# adc.net
KiCad netlist of a schematic drawn in EAGLE
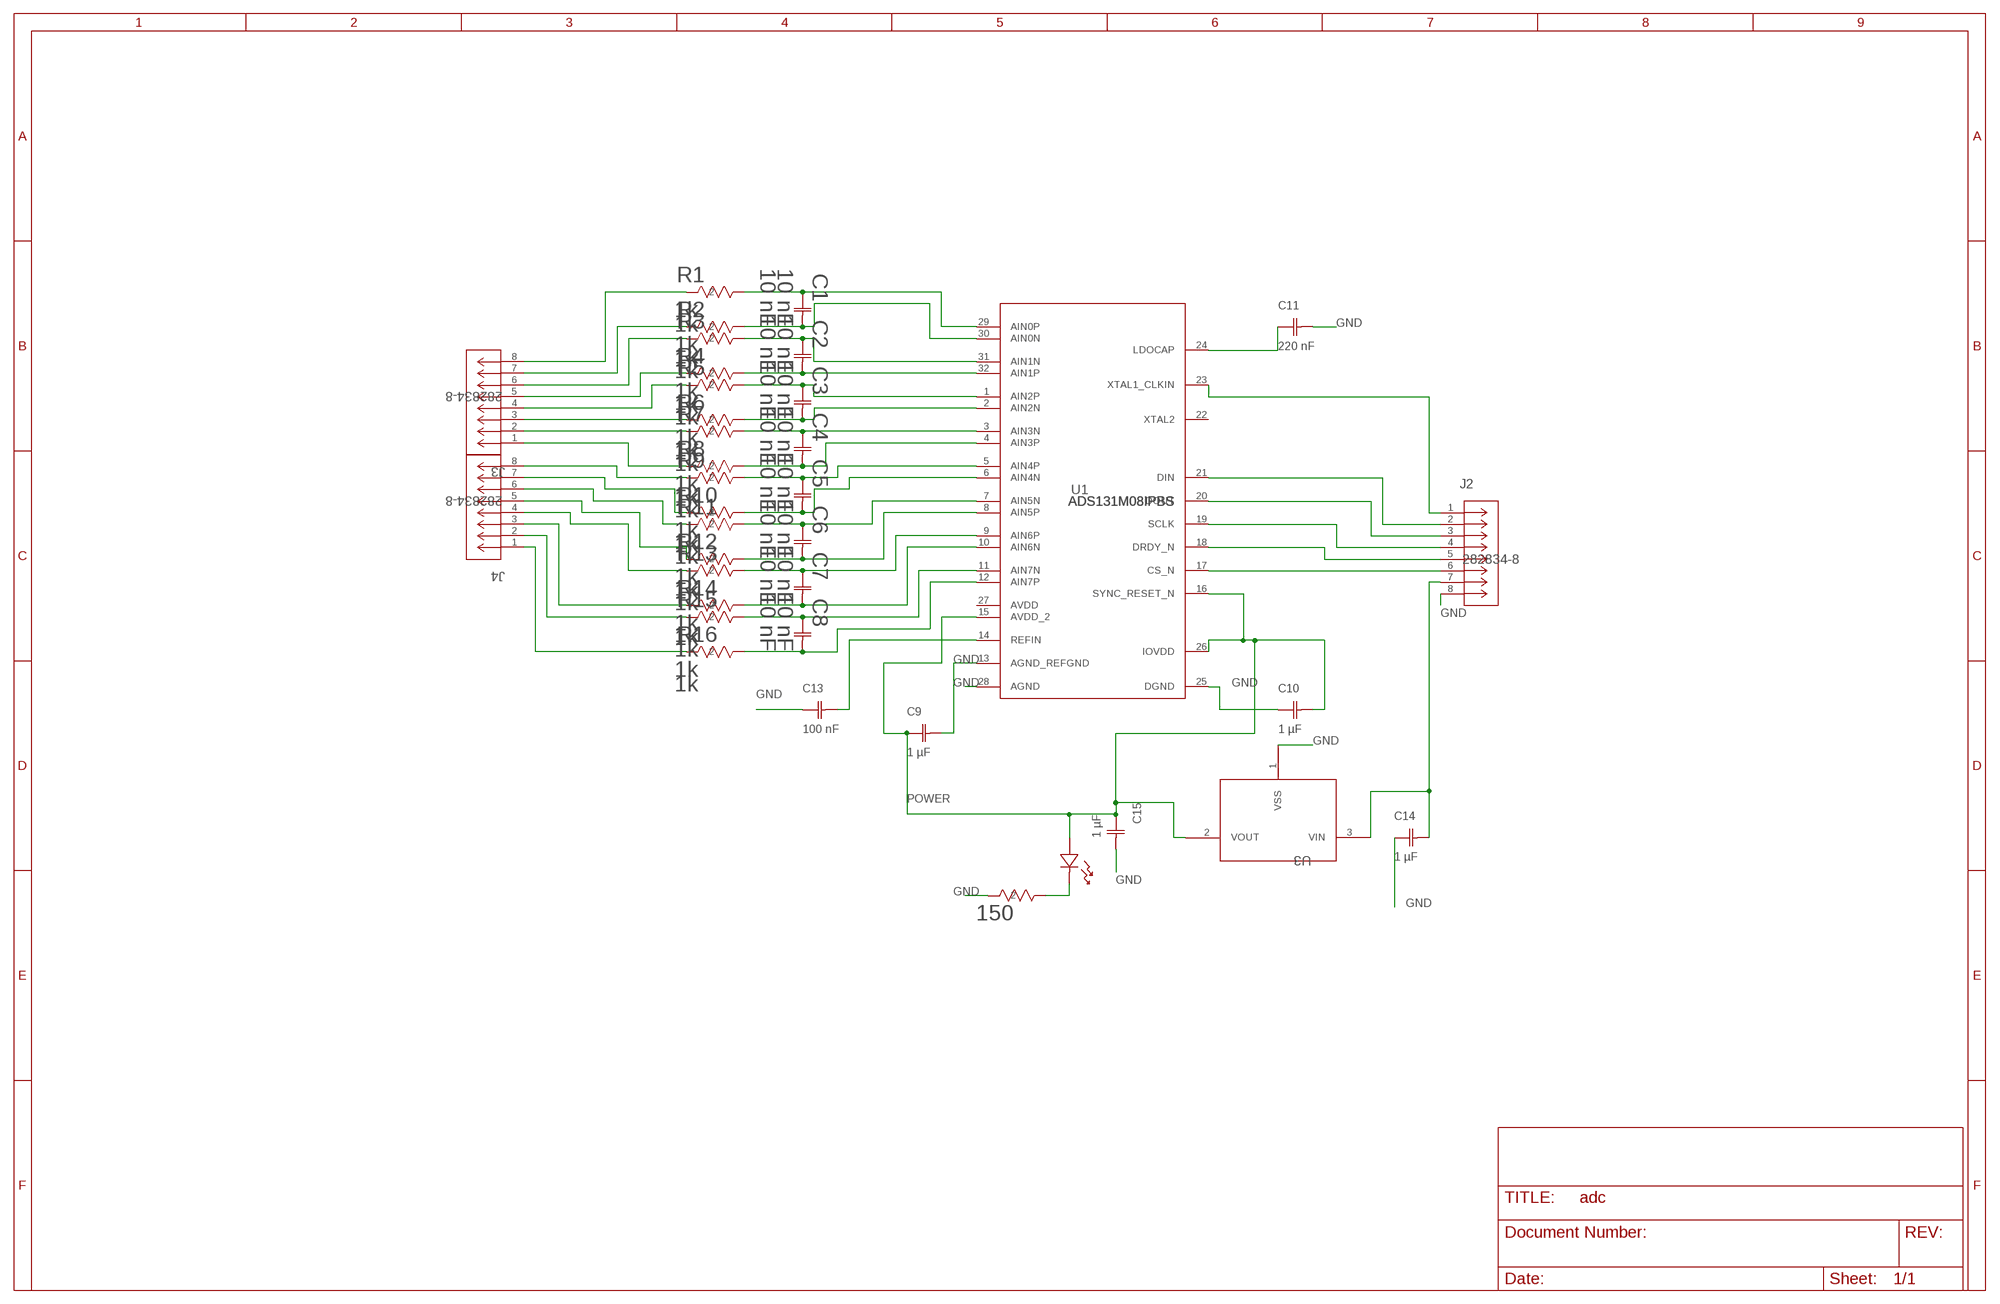
[diagram p0: schematic, sheet 1]

(export (version "E")
  (design (tool "Eeschema 10.0.6"))
  (components
    (comp (ref "C1")
      (value "10 nF")
      (footprint "eagle-import:CAPC220145_88N_KEM")
      (fields
        (field (name "MANUFACTURER_PART_NUMBER") "C0805C103K5RACAUTO")
        (field (name "COPYRIGHT") "Copyright (C) 2025 Ultra Librarian. All rights reserved.")
      )
      (libsource (lib "eagle-import") (part "C0805C103K5RACAUTO"))
    )
    (comp (ref "C2")
      (value "10 nF")
      (footprint "eagle-import:CAPC220145_88N_KEM")
      (fields
        (field (name "MANUFACTURER_PART_NUMBER") "C0805C103K5RACAUTO")
        (field (name "COPYRIGHT") "Copyright (C) 2025 Ultra Librarian. All rights reserved.")
      )
      (libsource (lib "eagle-import") (part "C0805C103K5RACAUTO"))
    )
    (comp (ref "C3")
      (value "10 nF")
      (footprint "eagle-import:CAPC220145_88N_KEM")
      (fields
        (field (name "MANUFACTURER_PART_NUMBER") "C0805C103K5RACAUTO")
        (field (name "COPYRIGHT") "Copyright (C) 2025 Ultra Librarian. All rights reserved.")
      )
      (libsource (lib "eagle-import") (part "C0805C103K5RACAUTO"))
    )
    (comp (ref "C4")
      (value "10 nF")
      (footprint "eagle-import:CAPC220145_88N_KEM")
      (fields
        (field (name "MANUFACTURER_PART_NUMBER") "C0805C103K5RACAUTO")
        (field (name "COPYRIGHT") "Copyright (C) 2025 Ultra Librarian. All rights reserved.")
      )
      (libsource (lib "eagle-import") (part "C0805C103K5RACAUTO"))
    )
    (comp (ref "C5")
      (value "10 nF")
      (footprint "eagle-import:CAPC220145_88N_KEM")
      (fields
        (field (name "MANUFACTURER_PART_NUMBER") "C0805C103K5RACAUTO")
        (field (name "COPYRIGHT") "Copyright (C) 2025 Ultra Librarian. All rights reserved.")
      )
      (libsource (lib "eagle-import") (part "C0805C103K5RACAUTO"))
    )
    (comp (ref "C6")
      (value "10 nF")
      (footprint "eagle-import:CAPC220145_88N_KEM")
      (fields
        (field (name "MANUFACTURER_PART_NUMBER") "C0805C103K5RACAUTO")
        (field (name "COPYRIGHT") "Copyright (C) 2025 Ultra Librarian. All rights reserved.")
      )
      (libsource (lib "eagle-import") (part "C0805C103K5RACAUTO"))
    )
    (comp (ref "C7")
      (value "10 nF")
      (footprint "eagle-import:CAPC220145_88N_KEM")
      (fields
        (field (name "MANUFACTURER_PART_NUMBER") "C0805C103K5RACAUTO")
        (field (name "COPYRIGHT") "Copyright (C) 2025 Ultra Librarian. All rights reserved.")
      )
      (libsource (lib "eagle-import") (part "C0805C103K5RACAUTO"))
    )
    (comp (ref "C8")
      (value "10 nF")
      (footprint "eagle-import:CAPC220145_88N_KEM")
      (fields
        (field (name "MANUFACTURER_PART_NUMBER") "C0805C103K5RACAUTO")
        (field (name "COPYRIGHT") "Copyright (C) 2025 Ultra Librarian. All rights reserved.")
      )
      (libsource (lib "eagle-import") (part "C0805C103K5RACAUTO"))
    )
    (comp (ref "C9")
      (value "1 µF")
      (footprint "eagle-import:CAPC220145_140N_KEM")
      (fields
        (field (name "MANUFACTURER_PART_NUMBER") "C0805C105K5RACTU")
        (field (name "COPYRIGHT") "Copyright (C) 2025 Ultra Librarian. All rights reserved.")
      )
      (libsource (lib "eagle-import") (part "C0805C105K5RACTU"))
    )
    (comp (ref "C10")
      (value "1 µF")
      (footprint "eagle-import:CAPC220145_140N_KEM")
      (fields
        (field (name "MANUFACTURER_PART_NUMBER") "C0805C105K5RACTU")
        (field (name "COPYRIGHT") "Copyright (C) 2025 Ultra Librarian. All rights reserved.")
      )
      (libsource (lib "eagle-import") (part "C0805C105K5RACTU"))
    )
    (comp (ref "C11")
      (value "220 nF")
      (footprint "eagle-import:CAPC220145_100N_KEM")
      (fields
        (field (name "MANUFACTURER_PART_NUMBER") "C0805C224K5RACAUTO")
        (field (name "COPYRIGHT") "Copyright (C) 2025 Ultra Librarian. All rights reserved.")
      )
      (libsource (lib "eagle-import") (part "C0805C224K5RACAUTO"))
    )
    (comp (ref "C13")
      (value "100 nF")
      (footprint "eagle-import:CAPC220145_88N_KEM")
      (fields
        (field (name "MANUFACTURER_PART_NUMBER") "C0805C104K5RACTU")
        (field (name "COPYRIGHT") "Copyright (C) 2025 Ultra Librarian. All rights reserved.")
      )
      (libsource (lib "eagle-import") (part "C0805C104K5RACTU"))
    )
    (comp (ref "C14")
      (value "1 µF")
      (footprint "eagle-import:CAPC220145_140N_KEM")
      (fields
        (field (name "MANUFACTURER_PART_NUMBER") "C0805C105K5RACTU")
        (field (name "COPYRIGHT") "Copyright (C) 2025 Ultra Librarian. All rights reserved.")
      )
      (libsource (lib "eagle-import") (part "C0805C105K5RACTU"))
    )
    (comp (ref "C15")
      (value "1 µF")
      (footprint "eagle-import:CAPC220145_140N_KEM")
      (fields
        (field (name "MANUFACTURER_PART_NUMBER") "C0805C105K5RACTU")
        (field (name "COPYRIGHT") "Copyright (C) 2025 Ultra Librarian. All rights reserved.")
      )
      (libsource (lib "eagle-import") (part "C0805C105K5RACTU"))
    )
    (comp (ref "J2")
      (value "282834-8")
      (footprint "eagle-import:CONN_282834-8_TEC")
      (fields (field (name "COPYRIGHT") "Copyright (C) 2025 Ultra Librarian. All rights reserved."))
      (libsource (lib "eagle-import") (part "282834-8"))
    )
    (comp (ref "J3")
      (value "282834-8")
      (footprint "eagle-import:CONN_282834-8_TEC")
      (fields (field (name "COPYRIGHT") "Copyright (C) 2025 Ultra Librarian. All rights reserved."))
      (libsource (lib "eagle-import") (part "282834-8"))
    )
    (comp (ref "J4")
      (value "282834-8")
      (footprint "eagle-import:CONN_282834-8_TEC")
      (fields (field (name "COPYRIGHT") "Copyright (C) 2025 Ultra Librarian. All rights reserved."))
      (libsource (lib "eagle-import") (part "282834-8"))
    )
    (comp (ref "LED1")
      (value "LTST-C190KFKT")
      (footprint "eagle-import:LED_LSTS-C190_LTO")
      (fields (field (name "COPYRIGHT") "Copyright (C) 2025 Ultra Librarian. All rights reserved."))
      (libsource (lib "eagle-import") (part "LTST-C190KFKT"))
    )
    (comp (ref "R1")
      (value "1k")
      (footprint "eagle-import:RC0402N_YAG-M")
      (fields
        (field (name "MANUFACTURER_PART_NUMBER") "RC0402JR-071KL")
        (field (name "COPYRIGHT") "Copyright (C) 2025 Ultra Librarian. All rights reserved.")
      )
      (libsource (lib "eagle-import") (part "RC0402JR-071KLRC0402N_YAG-M"))
    )
    (comp (ref "R2")
      (value "1k")
      (footprint "eagle-import:RC0402N_YAG-M")
      (fields
        (field (name "MANUFACTURER_PART_NUMBER") "RC0402JR-071KL")
        (field (name "COPYRIGHT") "Copyright (C) 2025 Ultra Librarian. All rights reserved.")
      )
      (libsource (lib "eagle-import") (part "RC0402JR-071KLRC0402N_YAG-M"))
    )
    (comp (ref "R3")
      (value "1k")
      (footprint "eagle-import:RC0402N_YAG-M")
      (fields
        (field (name "MANUFACTURER_PART_NUMBER") "RC0402JR-071KL")
        (field (name "COPYRIGHT") "Copyright (C) 2025 Ultra Librarian. All rights reserved.")
      )
      (libsource (lib "eagle-import") (part "RC0402JR-071KLRC0402N_YAG-M"))
    )
    (comp (ref "R4")
      (value "1k")
      (footprint "eagle-import:RC0402N_YAG-M")
      (fields
        (field (name "MANUFACTURER_PART_NUMBER") "RC0402JR-071KL")
        (field (name "COPYRIGHT") "Copyright (C) 2025 Ultra Librarian. All rights reserved.")
      )
      (libsource (lib "eagle-import") (part "RC0402JR-071KLRC0402N_YAG-M"))
    )
    (comp (ref "R5")
      (value "1k")
      (footprint "eagle-import:RC0402N_YAG-M")
      (fields
        (field (name "MANUFACTURER_PART_NUMBER") "RC0402JR-071KL")
        (field (name "COPYRIGHT") "Copyright (C) 2025 Ultra Librarian. All rights reserved.")
      )
      (libsource (lib "eagle-import") (part "RC0402JR-071KLRC0402N_YAG-M"))
    )
    (comp (ref "R6")
      (value "1k")
      (footprint "eagle-import:RC0402N_YAG-M")
      (fields
        (field (name "MANUFACTURER_PART_NUMBER") "RC0402JR-071KL")
        (field (name "COPYRIGHT") "Copyright (C) 2025 Ultra Librarian. All rights reserved.")
      )
      (libsource (lib "eagle-import") (part "RC0402JR-071KLRC0402N_YAG-M"))
    )
    (comp (ref "R7")
      (value "1k")
      (footprint "eagle-import:RC0402N_YAG-M")
      (fields
        (field (name "MANUFACTURER_PART_NUMBER") "RC0402JR-071KL")
        (field (name "COPYRIGHT") "Copyright (C) 2025 Ultra Librarian. All rights reserved.")
      )
      (libsource (lib "eagle-import") (part "RC0402JR-071KLRC0402N_YAG-M"))
    )
    (comp (ref "R8")
      (value "1k")
      (footprint "eagle-import:RC0402N_YAG-M")
      (fields
        (field (name "MANUFACTURER_PART_NUMBER") "RC0402JR-071KL")
        (field (name "COPYRIGHT") "Copyright (C) 2025 Ultra Librarian. All rights reserved.")
      )
      (libsource (lib "eagle-import") (part "RC0402JR-071KLRC0402N_YAG-M"))
    )
    (comp (ref "R9")
      (value "1k")
      (footprint "eagle-import:RC0402N_YAG-M")
      (fields
        (field (name "MANUFACTURER_PART_NUMBER") "RC0402JR-071KL")
        (field (name "COPYRIGHT") "Copyright (C) 2025 Ultra Librarian. All rights reserved.")
      )
      (libsource (lib "eagle-import") (part "RC0402JR-071KLRC0402N_YAG-M"))
    )
    (comp (ref "R10")
      (value "1k")
      (footprint "eagle-import:RC0402N_YAG-M")
      (fields
        (field (name "MANUFACTURER_PART_NUMBER") "RC0402JR-071KL")
        (field (name "COPYRIGHT") "Copyright (C) 2025 Ultra Librarian. All rights reserved.")
      )
      (libsource (lib "eagle-import") (part "RC0402JR-071KLRC0402N_YAG-M"))
    )
    (comp (ref "R11")
      (value "1k")
      (footprint "eagle-import:RC0402N_YAG-M")
      (fields
        (field (name "MANUFACTURER_PART_NUMBER") "RC0402JR-071KL")
        (field (name "COPYRIGHT") "Copyright (C) 2025 Ultra Librarian. All rights reserved.")
      )
      (libsource (lib "eagle-import") (part "RC0402JR-071KLRC0402N_YAG-M"))
    )
    (comp (ref "R12")
      (value "1k")
      (footprint "eagle-import:RC0402N_YAG-M")
      (fields
        (field (name "MANUFACTURER_PART_NUMBER") "RC0402JR-071KL")
        (field (name "COPYRIGHT") "Copyright (C) 2025 Ultra Librarian. All rights reserved.")
      )
      (libsource (lib "eagle-import") (part "RC0402JR-071KLRC0402N_YAG-M"))
    )
    (comp (ref "R13")
      (value "1k")
      (footprint "eagle-import:RC0402N_YAG-M")
      (fields
        (field (name "MANUFACTURER_PART_NUMBER") "RC0402JR-071KL")
        (field (name "COPYRIGHT") "Copyright (C) 2025 Ultra Librarian. All rights reserved.")
      )
      (libsource (lib "eagle-import") (part "RC0402JR-071KLRC0402N_YAG-M"))
    )
    (comp (ref "R14")
      (value "1k")
      (footprint "eagle-import:RC0402N_YAG-M")
      (fields
        (field (name "MANUFACTURER_PART_NUMBER") "RC0402JR-071KL")
        (field (name "COPYRIGHT") "Copyright (C) 2025 Ultra Librarian. All rights reserved.")
      )
      (libsource (lib "eagle-import") (part "RC0402JR-071KLRC0402N_YAG-M"))
    )
    (comp (ref "R15")
      (value "1k")
      (footprint "eagle-import:RC0402N_YAG-M")
      (fields
        (field (name "MANUFACTURER_PART_NUMBER") "RC0402JR-071KL")
        (field (name "COPYRIGHT") "Copyright (C) 2025 Ultra Librarian. All rights reserved.")
      )
      (libsource (lib "eagle-import") (part "RC0402JR-071KLRC0402N_YAG-M"))
    )
    (comp (ref "R16")
      (value "1k")
      (footprint "eagle-import:RC0402N_YAG-M")
      (fields
        (field (name "MANUFACTURER_PART_NUMBER") "RC0402JR-071KL")
        (field (name "COPYRIGHT") "Copyright (C) 2025 Ultra Librarian. All rights reserved.")
      )
      (libsource (lib "eagle-import") (part "RC0402JR-071KLRC0402N_YAG-M"))
    )
    (comp (ref "R18")
      (value "150")
      (footprint "eagle-import:RC0402N_YAG-M")
      (fields
        (field (name "MANUFACTURER_PART_NUMBER") "RC0402JR-07150RL")
        (field (name "COPYRIGHT") "Copyright (C) 2025 Ultra Librarian. All rights reserved.")
      )
      (libsource (lib "eagle-import") (part "RC0402JR-07150RLRC0402N_YAG-M"))
    )
    (comp (ref "U1")
      (value "ADS131M08IPBS")
      (footprint "eagle-import:PBS0032A_N")
      (fields (field (name "COPYRIGHT") "Copyright (C) 2025 Ultra Librarian. All rights reserved."))
      (libsource (lib "eagle-import") (part "ADS131M08IPBS"))
    )
    (comp (ref "U3")
      (value "XC6206P332MR-GSOT-23_TOR-L")
      (footprint "eagle-import:SOT-23_TOR-L")
      (fields
        (field (name "MANUFACTURER_PART_NUMBER") "XC6206P332MR-G")
        (field (name "COPYRIGHT") "Copyright (C) 2025 Ultra Librarian. All rights reserved.")
      )
      (libsource (lib "eagle-import") (part "XC6206P332MR-GSOT-23_TOR-L"))
    )
  )
  (nets
    (net (code "1") (name "/AVDD") (class "Default")
      (node (ref "U1") (pin "27") (pinfunction "AVDD_27") (pintype "power_in"))
    )
    (net (code "2") (name "/GND") (class "Default")
      (node (ref "C10") (pin "1") (pinfunction "1_1") (pintype "passive"))
      (node (ref "C11") (pin "2") (pinfunction "2_2") (pintype "passive"))
      (node (ref "C13") (pin "1") (pinfunction "1_1") (pintype "passive"))
      (node (ref "C14") (pin "1") (pinfunction "1_1") (pintype "passive"))
      (node (ref "C15") (pin "2") (pinfunction "2_2") (pintype "passive"))
      (node (ref "C9") (pin "2") (pinfunction "2_2") (pintype "passive"))
      (node (ref "J2") (pin "8") (pinfunction "8_8") (pintype "passive"))
      (node (ref "R18") (pin "2") (pinfunction "2_2") (pintype "passive"))
      (node (ref "U1") (pin "13") (pinfunction "AGND_REFGND_13") (pintype "power_in"))
      (node (ref "U1") (pin "25") (pinfunction "DGND_25") (pintype "power_in"))
      (node (ref "U1") (pin "28") (pinfunction "AGND_28") (pintype "power_in"))
      (node (ref "U3") (pin "1") (pinfunction "VSS_1") (pintype "passive"))
    )
    (net (code "3") (name "/POWER") (class "Default")
      (node (ref "C10") (pin "2") (pinfunction "2_2") (pintype "passive"))
      (node (ref "C15") (pin "1") (pinfunction "1_1") (pintype "passive"))
      (node (ref "C9") (pin "1") (pinfunction "1_1") (pintype "passive"))
      (node (ref "LED1") (pin "2") (pinfunction "ANODE_2") (pintype "passive"))
      (node (ref "U1") (pin "15") (pinfunction "AVDD_2_15") (pintype "power_in"))
      (node (ref "U1") (pin "16") (pinfunction "SYNC_RESET_N_16") (pintype "input"))
      (node (ref "U1") (pin "26") (pinfunction "IOVDD_26") (pintype "power_in"))
      (node (ref "U3") (pin "2") (pinfunction "VOUT_2") (pintype "output"))
    )
    (net (code "4") (name "Net-(J3-Pad1)") (class "Default")
      (node (ref "J3") (pin "1") (pinfunction "1_1") (pintype "passive"))
      (node (ref "R8") (pin "2") (pinfunction "2_2") (pintype "passive"))
    )
    (net (code "5") (name "Net-(J3-Pad2)") (class "Default")
      (node (ref "J3") (pin "2") (pinfunction "2_2") (pintype "passive"))
      (node (ref "R7") (pin "2") (pinfunction "2_2") (pintype "passive"))
    )
    (net (code "6") (name "Net-(J3-Pad3)") (class "Default")
      (node (ref "J3") (pin "3") (pinfunction "3_3") (pintype "passive"))
      (node (ref "R6") (pin "2") (pinfunction "2_2") (pintype "passive"))
    )
    (net (code "7") (name "Net-(J3-Pad4)") (class "Default")
      (node (ref "J3") (pin "4") (pinfunction "4_4") (pintype "passive"))
      (node (ref "R5") (pin "2") (pinfunction "2_2") (pintype "passive"))
    )
    (net (code "8") (name "Net-(J3-Pad5)") (class "Default")
      (node (ref "J3") (pin "5") (pinfunction "5_5") (pintype "passive"))
      (node (ref "R4") (pin "2") (pinfunction "2_2") (pintype "passive"))
    )
    (net (code "9") (name "Net-(J3-Pad6)") (class "Default")
      (node (ref "J3") (pin "6") (pinfunction "6_6") (pintype "passive"))
      (node (ref "R3") (pin "2") (pinfunction "2_2") (pintype "passive"))
    )
    (net (code "10") (name "Net-(J3-Pad7)") (class "Default")
      (node (ref "J3") (pin "7") (pinfunction "7_7") (pintype "passive"))
      (node (ref "R2") (pin "2") (pinfunction "2_2") (pintype "passive"))
    )
    (net (code "11") (name "Net-(J3-Pad8)") (class "Default")
      (node (ref "J3") (pin "8") (pinfunction "8_8") (pintype "passive"))
      (node (ref "R1") (pin "2") (pinfunction "2_2") (pintype "passive"))
    )
    (net (code "12") (name "Net-(J4-Pad1)") (class "Default")
      (node (ref "J4") (pin "1") (pinfunction "1_1") (pintype "passive"))
      (node (ref "R16") (pin "2") (pinfunction "2_2") (pintype "passive"))
    )
    (net (code "13") (name "Net-(J4-Pad2)") (class "Default")
      (node (ref "J4") (pin "2") (pinfunction "2_2") (pintype "passive"))
      (node (ref "R15") (pin "2") (pinfunction "2_2") (pintype "passive"))
    )
    (net (code "14") (name "Net-(J4-Pad3)") (class "Default")
      (node (ref "J4") (pin "3") (pinfunction "3_3") (pintype "passive"))
      (node (ref "R14") (pin "2") (pinfunction "2_2") (pintype "passive"))
    )
    (net (code "15") (name "Net-(J4-Pad4)") (class "Default")
      (node (ref "J4") (pin "4") (pinfunction "4_4") (pintype "passive"))
      (node (ref "R13") (pin "2") (pinfunction "2_2") (pintype "passive"))
    )
    (net (code "16") (name "Net-(J4-Pad5)") (class "Default")
      (node (ref "J4") (pin "5") (pinfunction "5_5") (pintype "passive"))
      (node (ref "R12") (pin "2") (pinfunction "2_2") (pintype "passive"))
    )
    (net (code "17") (name "Net-(J4-Pad6)") (class "Default")
      (node (ref "J4") (pin "6") (pinfunction "6_6") (pintype "passive"))
      (node (ref "R11") (pin "2") (pinfunction "2_2") (pintype "passive"))
    )
    (net (code "18") (name "Net-(J4-Pad7)") (class "Default")
      (node (ref "J4") (pin "7") (pinfunction "7_7") (pintype "passive"))
      (node (ref "R10") (pin "2") (pinfunction "2_2") (pintype "passive"))
    )
    (net (code "19") (name "Net-(J4-Pad8)") (class "Default")
      (node (ref "J4") (pin "8") (pinfunction "8_8") (pintype "passive"))
      (node (ref "R9") (pin "2") (pinfunction "2_2") (pintype "passive"))
    )
    (net (code "20") (name "Net-(LED1-CATHODE)") (class "Default")
      (node (ref "LED1") (pin "1") (pinfunction "CATHODE_1") (pintype "passive"))
      (node (ref "R18") (pin "1") (pinfunction "1_1") (pintype "passive"))
    )
    (net (code "21") (name "Net-(U1-AIN0N)") (class "Default")
      (node (ref "C1") (pin "2") (pinfunction "2_2") (pintype "passive"))
      (node (ref "R2") (pin "1") (pinfunction "1_1") (pintype "passive"))
      (node (ref "U1") (pin "30") (pinfunction "AIN0N_30") (pintype "input"))
    )
    (net (code "22") (name "Net-(U1-AIN0P)") (class "Default")
      (node (ref "C1") (pin "1") (pinfunction "1_1") (pintype "passive"))
      (node (ref "R1") (pin "1") (pinfunction "1_1") (pintype "passive"))
      (node (ref "U1") (pin "29") (pinfunction "AIN0P_29") (pintype "input"))
    )
    (net (code "23") (name "Net-(U1-AIN1N)") (class "Default")
      (node (ref "C2") (pin "1") (pinfunction "1_1") (pintype "passive"))
      (node (ref "R3") (pin "1") (pinfunction "1_1") (pintype "passive"))
      (node (ref "U1") (pin "31") (pinfunction "AIN1N_31") (pintype "input"))
    )
    (net (code "24") (name "Net-(U1-AIN1P)") (class "Default")
      (node (ref "C2") (pin "2") (pinfunction "2_2") (pintype "passive"))
      (node (ref "R4") (pin "1") (pinfunction "1_1") (pintype "passive"))
      (node (ref "U1") (pin "32") (pinfunction "AIN1P_32") (pintype "input"))
    )
    (net (code "25") (name "Net-(U1-AIN2N)") (class "Default")
      (node (ref "C3") (pin "2") (pinfunction "2_2") (pintype "passive"))
      (node (ref "R6") (pin "1") (pinfunction "1_1") (pintype "passive"))
      (node (ref "U1") (pin "2") (pinfunction "AIN2N_2") (pintype "input"))
    )
    (net (code "26") (name "Net-(U1-AIN2P)") (class "Default")
      (node (ref "C3") (pin "1") (pinfunction "1_1") (pintype "passive"))
      (node (ref "R5") (pin "1") (pinfunction "1_1") (pintype "passive"))
      (node (ref "U1") (pin "1") (pinfunction "AIN2P_1") (pintype "input"))
    )
    (net (code "27") (name "Net-(U1-AIN3N)") (class "Default")
      (node (ref "C4") (pin "1") (pinfunction "1_1") (pintype "passive"))
      (node (ref "R7") (pin "1") (pinfunction "1_1") (pintype "passive"))
      (node (ref "U1") (pin "3") (pinfunction "AIN3N_3") (pintype "input"))
    )
    (net (code "28") (name "Net-(U1-AIN3P)") (class "Default")
      (node (ref "C4") (pin "2") (pinfunction "2_2") (pintype "passive"))
      (node (ref "R8") (pin "1") (pinfunction "1_1") (pintype "passive"))
      (node (ref "U1") (pin "4") (pinfunction "AIN3P_4") (pintype "input"))
    )
    (net (code "29") (name "Net-(U1-AIN4N)") (class "Default")
      (node (ref "C5") (pin "2") (pinfunction "2_2") (pintype "passive"))
      (node (ref "R10") (pin "1") (pinfunction "1_1") (pintype "passive"))
      (node (ref "U1") (pin "6") (pinfunction "AIN4N_6") (pintype "input"))
    )
    (net (code "30") (name "Net-(U1-AIN4P)") (class "Default")
      (node (ref "C5") (pin "1") (pinfunction "1_1") (pintype "passive"))
      (node (ref "R9") (pin "1") (pinfunction "1_1") (pintype "passive"))
      (node (ref "U1") (pin "5") (pinfunction "AIN4P_5") (pintype "input"))
    )
    (net (code "31") (name "Net-(U1-AIN5N)") (class "Default")
      (node (ref "C6") (pin "1") (pinfunction "1_1") (pintype "passive"))
      (node (ref "R11") (pin "1") (pinfunction "1_1") (pintype "passive"))
      (node (ref "U1") (pin "7") (pinfunction "AIN5N_7") (pintype "input"))
    )
    (net (code "32") (name "Net-(U1-AIN5P)") (class "Default")
      (node (ref "C6") (pin "2") (pinfunction "2_2") (pintype "passive"))
      (node (ref "R12") (pin "1") (pinfunction "1_1") (pintype "passive"))
      (node (ref "U1") (pin "8") (pinfunction "AIN5P_8") (pintype "input"))
    )
    (net (code "33") (name "Net-(U1-AIN6N)") (class "Default")
      (node (ref "C7") (pin "2") (pinfunction "2_2") (pintype "passive"))
      (node (ref "R14") (pin "1") (pinfunction "1_1") (pintype "passive"))
      (node (ref "U1") (pin "10") (pinfunction "AIN6N_10") (pintype "input"))
    )
    (net (code "34") (name "Net-(U1-AIN6P)") (class "Default")
      (node (ref "C7") (pin "1") (pinfunction "1_1") (pintype "passive"))
      (node (ref "R13") (pin "1") (pinfunction "1_1") (pintype "passive"))
      (node (ref "U1") (pin "9") (pinfunction "AIN6P_9") (pintype "input"))
    )
    (net (code "35") (name "Net-(U1-AIN7N)") (class "Default")
      (node (ref "C8") (pin "1") (pinfunction "1_1") (pintype "passive"))
      (node (ref "R15") (pin "1") (pinfunction "1_1") (pintype "passive"))
      (node (ref "U1") (pin "11") (pinfunction "AIN7N_11") (pintype "input"))
    )
    (net (code "36") (name "Net-(U1-AIN7P)") (class "Default")
      (node (ref "C8") (pin "2") (pinfunction "2_2") (pintype "passive"))
      (node (ref "R16") (pin "1") (pinfunction "1_1") (pintype "passive"))
      (node (ref "U1") (pin "12") (pinfunction "AIN7P_12") (pintype "input"))
    )
    (net (code "37") (name "Net-(U1-CS_N)") (class "Default")
      (node (ref "J2") (pin "6") (pinfunction "6_6") (pintype "passive"))
      (node (ref "U1") (pin "17") (pinfunction "CS_N_17") (pintype "input"))
    )
    (net (code "38") (name "Net-(U1-DIN)") (class "Default")
      (node (ref "J2") (pin "2") (pinfunction "2_2") (pintype "passive"))
      (node (ref "U1") (pin "21") (pinfunction "DIN_21") (pintype "input"))
    )
    (net (code "39") (name "Net-(U1-DOUT)") (class "Default")
      (node (ref "J2") (pin "3") (pinfunction "3_3") (pintype "passive"))
      (node (ref "U1") (pin "20") (pinfunction "DOUT_20") (pintype "output"))
    )
    (net (code "40") (name "Net-(U1-DRDY_N)") (class "Default")
      (node (ref "J2") (pin "5") (pinfunction "5_5") (pintype "passive"))
      (node (ref "U1") (pin "18") (pinfunction "DRDY_N_18") (pintype "output"))
    )
    (net (code "41") (name "Net-(U1-LDOCAP)") (class "Default")
      (node (ref "C11") (pin "1") (pinfunction "1_1") (pintype "passive"))
      (node (ref "U1") (pin "24") (pinfunction "LDOCAP_24") (pintype "passive"))
    )
    (net (code "42") (name "Net-(U1-REFIN)") (class "Default")
      (node (ref "C13") (pin "2") (pinfunction "2_2") (pintype "passive"))
      (node (ref "U1") (pin "14") (pinfunction "REFIN_14") (pintype "input"))
    )
    (net (code "43") (name "Net-(U1-SCLK)") (class "Default")
      (node (ref "J2") (pin "4") (pinfunction "4_4") (pintype "passive"))
      (node (ref "U1") (pin "19") (pinfunction "SCLK_19") (pintype "input"))
    )
    (net (code "44") (name "Net-(U1-XTAL1_CLKIN)") (class "Default")
      (node (ref "J2") (pin "1") (pinfunction "1_1") (pintype "passive"))
      (node (ref "U1") (pin "23") (pinfunction "XTAL1_CLKIN_23") (pintype "input"))
    )
    (net (code "45") (name "Net-(U3-VIN)") (class "Default")
      (node (ref "C14") (pin "2") (pinfunction "2_2") (pintype "passive"))
      (node (ref "J2") (pin "7") (pinfunction "7_7") (pintype "passive"))
      (node (ref "U3") (pin "3") (pinfunction "VIN_3") (pintype "power_in"))
    )
    (net (code "46") (name "unconnected-(U1-XTAL2-Pad22)") (class "Default")
      (node (ref "U1") (pin "22") (pinfunction "XTAL2_22") (pintype "input"))
    )
  )
)
